# Regulators.net
KiCad netlist of a schematic drawn in Altium Designer
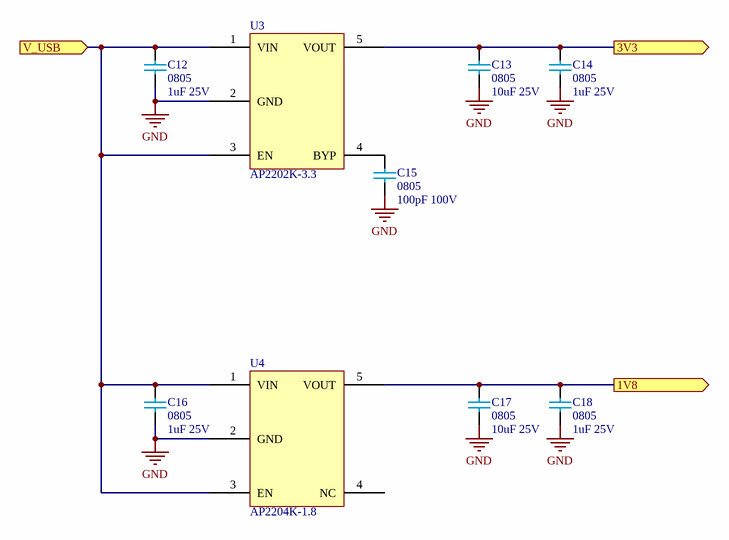
[diagram p0: Regulators.SchDoc]

(export (version "E")
  (design (tool "Eeschema 10.0.6"))
  (components
    (comp (ref "C12")
      (value "0805")
      (footprint "0805")
      (description "0805, X5R or better")
      (fields (field (name "ALTIUM_VALUE") "1uF 25V"))
      (libsource (lib "Chip_Passives") (part "Cap 1uF 25V"))
    )
    (comp (ref "C13")
      (value "0805")
      (footprint "0805")
      (description "0805, X5R or better")
      (fields (field (name "ALTIUM_VALUE") "10uF 25V"))
      (libsource (lib "Chip_Passives") (part "Cap 10uF 25V"))
    )
    (comp (ref "C14")
      (value "0805")
      (footprint "0805")
      (description "0805, X5R or better")
      (fields (field (name "ALTIUM_VALUE") "1uF 25V"))
      (libsource (lib "Chip_Passives") (part "Cap 1uF 25V"))
    )
    (comp (ref "C15")
      (value "0805")
      (footprint "0805")
      (description "0805, X5R or better")
      (fields (field (name "ALTIUM_VALUE") "100pF 100V"))
      (libsource (lib "Chip_Passives") (part "Cap 100pF 100V"))
    )
    (comp (ref "C16")
      (value "0805")
      (footprint "0805")
      (description "0805, X5R or better")
      (fields (field (name "ALTIUM_VALUE") "1uF 25V"))
      (libsource (lib "Chip_Passives") (part "Cap 1uF 25V"))
    )
    (comp (ref "C17")
      (value "0805")
      (footprint "0805")
      (description "0805, X5R or better")
      (fields (field (name "ALTIUM_VALUE") "10uF 25V"))
      (libsource (lib "Chip_Passives") (part "Cap 10uF 25V"))
    )
    (comp (ref "C18")
      (value "0805")
      (footprint "0805")
      (description "0805, X5R or better")
      (fields (field (name "ALTIUM_VALUE") "1uF 25V"))
      (libsource (lib "Chip_Passives") (part "Cap 1uF 25V"))
    )
    (comp (ref "U3")
      (value "AP2202K-3.3")
      (footprint "AP2202 - SOT95P270X145-5N")
      (description "3.3V 150mA LDO regulator")
      (libsource (lib "PowerSupply") (part "AP2202K-3.3"))
    )
    (comp (ref "U4")
      (value "AP2204K-1.8")
      (footprint "AP2202 - SOT95P270X145-5N")
      (description "Linear Voltage Regulator IC 1 Output 150mA SOT-23-5")
      (libsource (lib "PowerSupply") (part "AP2204K-1.8"))
    )
  )
  (nets
    (net (code "1") (name "/1V8") (class "Default")
      (node (ref "C17") (pin "2") (pinfunction "2_2") (pintype "passive"))
      (node (ref "C18") (pin "2") (pinfunction "2_2") (pintype "passive"))
      (node (ref "U4") (pin "5") (pinfunction "VOUT_5") (pintype "passive"))
    )
    (net (code "2") (name "/3V3") (class "Default")
      (node (ref "C13") (pin "2") (pinfunction "2_2") (pintype "passive"))
      (node (ref "C14") (pin "2") (pinfunction "2_2") (pintype "passive"))
      (node (ref "U3") (pin "5") (pinfunction "VOUT_5") (pintype "passive"))
    )
    (net (code "3") (name "/V_USB") (class "Default")
      (node (ref "C12") (pin "2") (pinfunction "2_2") (pintype "passive"))
      (node (ref "C16") (pin "2") (pinfunction "2_2") (pintype "passive"))
      (node (ref "U3") (pin "1") (pinfunction "VIN_1") (pintype "passive"))
      (node (ref "U3") (pin "3") (pinfunction "EN_3") (pintype "passive"))
      (node (ref "U4") (pin "1") (pinfunction "VIN_1") (pintype "passive"))
      (node (ref "U4") (pin "3") (pinfunction "EN_3") (pintype "passive"))
    )
    (net (code "4") (name "GND") (class "Default")
      (node (ref "C12") (pin "1") (pinfunction "1_1") (pintype "passive"))
      (node (ref "C13") (pin "1") (pinfunction "1_1") (pintype "passive"))
      (node (ref "C14") (pin "1") (pinfunction "1_1") (pintype "passive"))
      (node (ref "C15") (pin "1") (pinfunction "1_1") (pintype "passive"))
      (node (ref "C16") (pin "1") (pinfunction "1_1") (pintype "passive"))
      (node (ref "C17") (pin "1") (pinfunction "1_1") (pintype "passive"))
      (node (ref "C18") (pin "1") (pinfunction "1_1") (pintype "passive"))
      (node (ref "U3") (pin "2") (pinfunction "GND_2") (pintype "passive"))
      (node (ref "U4") (pin "2") (pinfunction "GND_2") (pintype "passive"))
    )
    (net (code "5") (name "Net-(U3-BYP)") (class "Default")
      (node (ref "C15") (pin "2") (pinfunction "2_2") (pintype "passive"))
      (node (ref "U3") (pin "4") (pinfunction "BYP_4") (pintype "passive"))
    )
    (net (code "6") (name "unconnected-(U4-NC-Pad4)") (class "Default")
      (node (ref "U4") (pin "4") (pinfunction "NC_4") (pintype "passive"))
    )
  )
)
